# MINI_SAM_2017-01-010.net
KiCad netlist of a schematic drawn in EAGLE
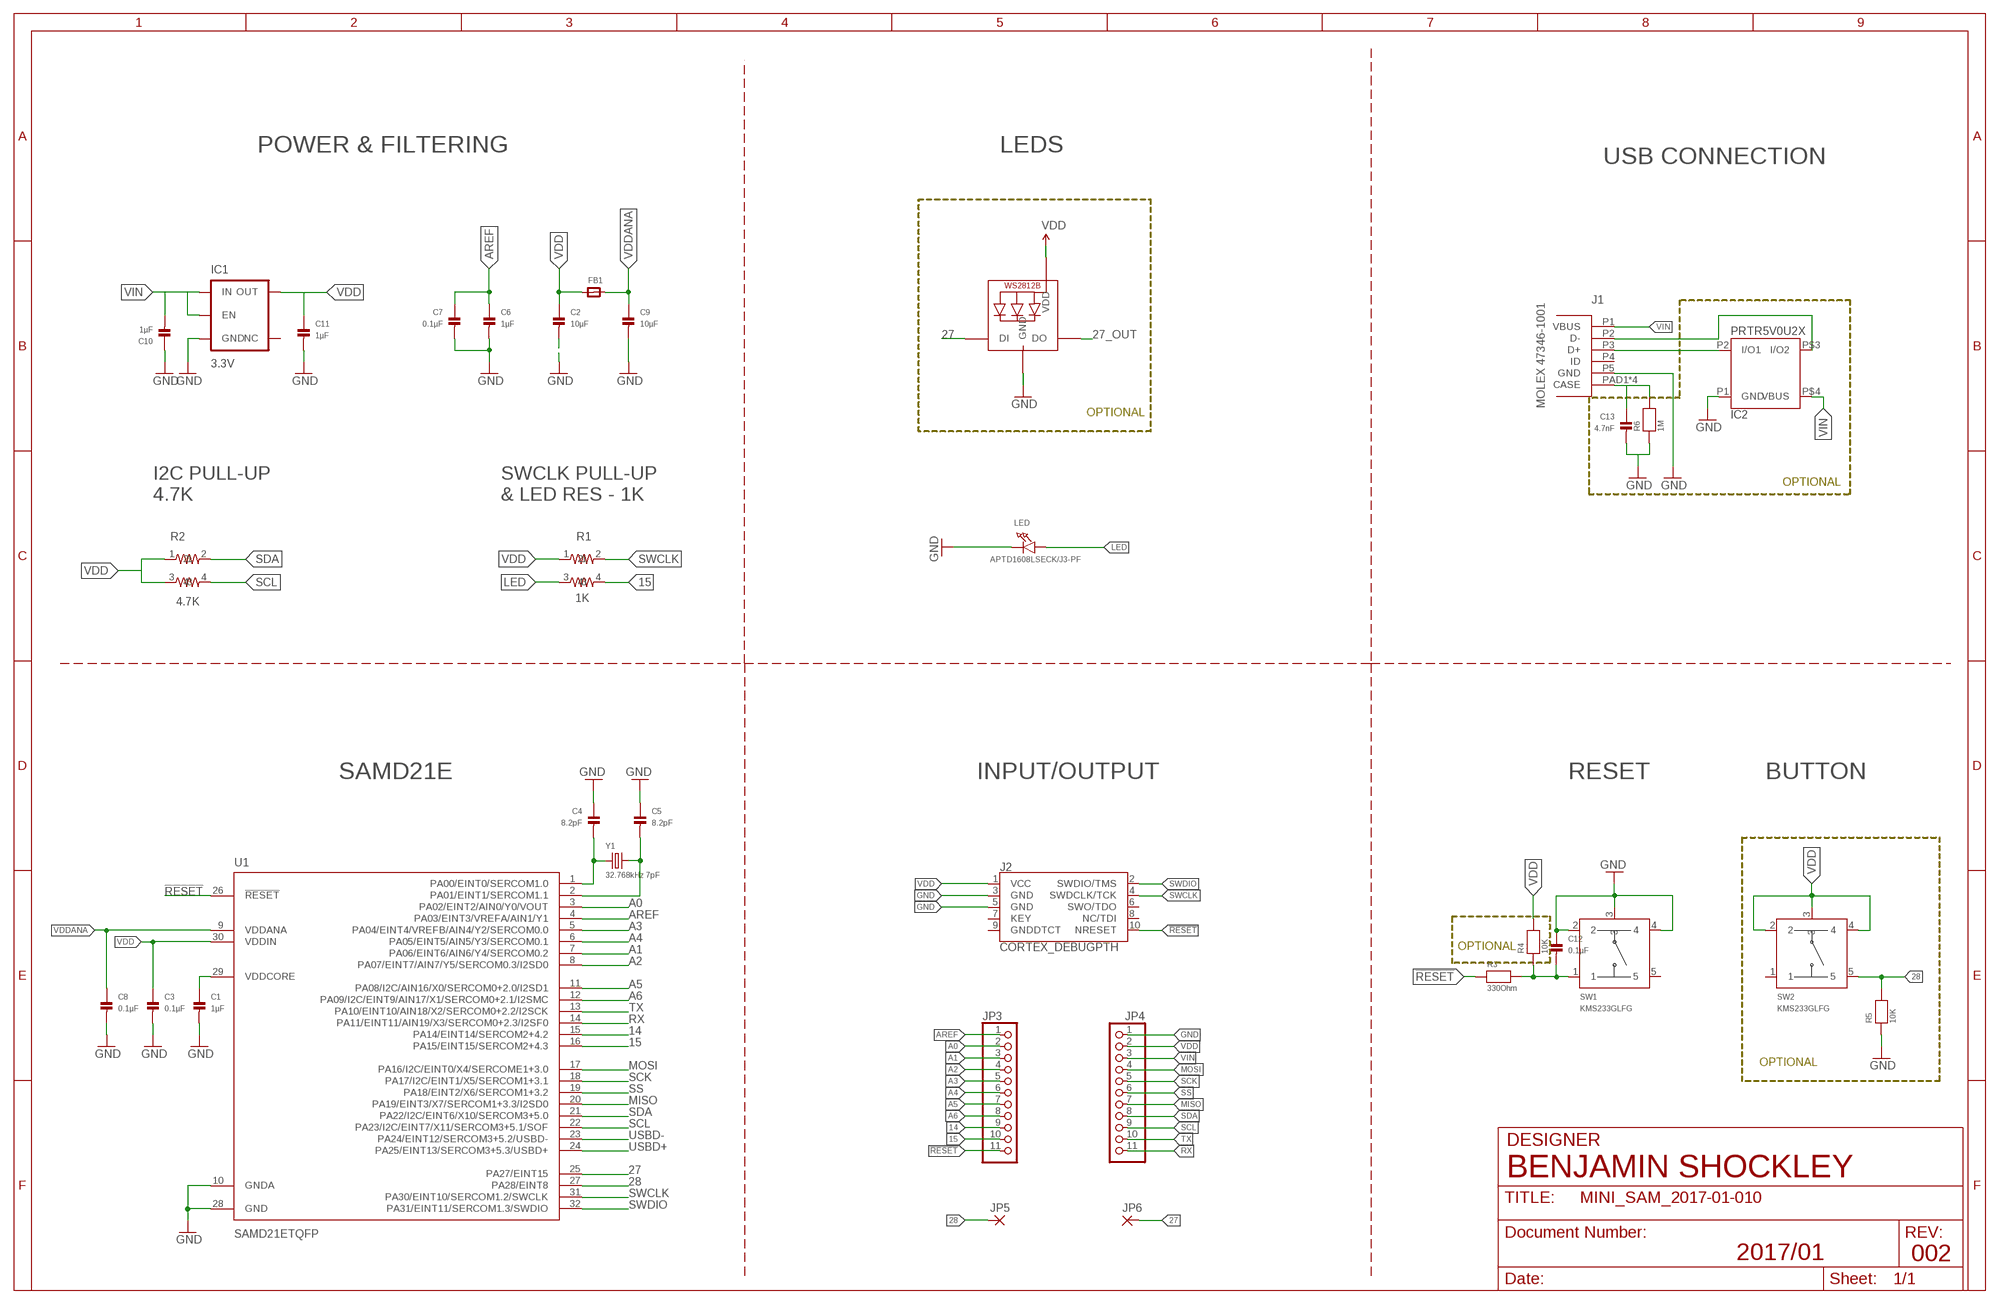
[diagram p0: schematic, sheet 1]

(export (version "E")
  (design (tool "Eeschema 10.0.6"))
  (components
    (comp (ref "C1")
      (value "1µF")
      (footprint "eagle-import:_0805MP")
      (libsource (lib "eagle-import") (part "CAP_CERAMIC_0805MP"))
    )
    (comp (ref "C2")
      (value "10µF")
      (footprint "eagle-import:_0805MP")
      (libsource (lib "eagle-import") (part "CAP_CERAMIC_0805MP"))
    )
    (comp (ref "C3")
      (value "0.1µF")
      (footprint "eagle-import:_0805MP")
      (libsource (lib "eagle-import") (part "CAP_CERAMIC_0805MP"))
    )
    (comp (ref "C4")
      (value "8.2pF")
      (footprint "eagle-import:_0805MP")
      (libsource (lib "eagle-import") (part "CAP_CERAMIC_0805MP"))
    )
    (comp (ref "C5")
      (value "8.2pF")
      (footprint "eagle-import:_0805MP")
      (libsource (lib "eagle-import") (part "CAP_CERAMIC_0805MP"))
    )
    (comp (ref "C6")
      (value "1µF")
      (footprint "eagle-import:_0805MP")
      (libsource (lib "eagle-import") (part "CAP_CERAMIC_0805MP"))
    )
    (comp (ref "C7")
      (value "0.1µF")
      (footprint "eagle-import:_0805MP")
      (libsource (lib "eagle-import") (part "CAP_CERAMIC_0805MP"))
    )
    (comp (ref "C8")
      (value "0.1µF")
      (footprint "eagle-import:_0805MP")
      (libsource (lib "eagle-import") (part "CAP_CERAMIC_0805MP"))
    )
    (comp (ref "C9")
      (value "10µF")
      (footprint "eagle-import:_0805MP")
      (libsource (lib "eagle-import") (part "CAP_CERAMIC_0805MP"))
    )
    (comp (ref "C10")
      (value "1µF")
      (footprint "eagle-import:_0805MP")
      (libsource (lib "eagle-import") (part "CAP_CERAMIC_0805MP"))
    )
    (comp (ref "C11")
      (value "1µF")
      (footprint "eagle-import:_0805MP")
      (libsource (lib "eagle-import") (part "CAP_CERAMIC_0805MP"))
    )
    (comp (ref "C12")
      (value "0.1µF")
      (footprint "eagle-import:_0805MP")
      (libsource (lib "eagle-import") (part "CAP_CERAMIC_0805MP"))
    )
    (comp (ref "C13")
      (value "4.7nF")
      (footprint "eagle-import:_0805MP")
      (libsource (lib "eagle-import") (part "CAP_CERAMIC_0805MP"))
    )
    (comp (ref "FB1")
      (value "FERRITE_0805MP")
      (footprint "eagle-import:_0805MP")
      (libsource (lib "eagle-import") (part "FERRITE_0805MP"))
    )
    (comp (ref "IC1")
      (value "3.3V")
      (footprint "eagle-import:SOT23-5")
      (libsource (lib "eagle-import") (part "V_REG_AP2112K-3.3V"))
    )
    (comp (ref "IC2")
      (value "PRTR5V0U2X")
      (footprint "eagle-import:SOT143B_REFLOW")
      (libsource (lib "eagle-import") (part "PRTR5V0U2X"))
    )
    (comp (ref "J1")
      (value "MOLEX_47346-100147346")
      (footprint "eagle-import:MOLEX_47346-1001")
      (libsource (lib "eagle-import") (part "MOLEX_47346-100147346"))
    )
    (comp (ref "J2")
      (value "CORTEX_DEBUGPTH")
      (footprint "eagle-import:2X5-PTH-1.27MM")
      (libsource (lib "eagle-import") (part "CORTEX_DEBUGPTH"))
    )
    (comp (ref "JP3")
      (value "PINHD-1X111X11_SMT")
      (footprint "eagle-import:1X11_SMT")
      (libsource (lib "eagle-import") (part "PINHD-1X111X11_SMT"))
    )
    (comp (ref "JP4")
      (value "PINHD-1X111X11_SMT")
      (footprint "eagle-import:1X11_SMT")
      (libsource (lib "eagle-import") (part "PINHD-1X111X11_SMT"))
    )
    (comp (ref "JP5")
      (value "FR11_PAD2MMX1MM")
      (footprint "eagle-import:SMD2MMX1MM")
      (libsource (lib "eagle-import") (part "FR11_PAD2MMX1MM"))
    )
    (comp (ref "JP6")
      (value "FR11_PAD2MMX1MM")
      (footprint "eagle-import:SMD2MMX1MM")
      (libsource (lib "eagle-import") (part "FR11_PAD2MMX1MM"))
    )
    (comp (ref "LED")
      (value "APTD1608LSECK/J3-PF")
      (footprint "eagle-import:CHIPLED_0603_NOOUTLINE")
      (libsource (lib "eagle-import") (part "LED0603_NOOUTLINE"))
    )
    (comp (ref "R1")
      (value "1K")
      (footprint "eagle-import:RESISTOR_ARRAY_0606")
      (libsource (lib "eagle-import") (part "RESISTOR_ARRAY_2"))
    )
    (comp (ref "R2")
      (value "4.7K")
      (footprint "eagle-import:RESISTOR_ARRAY_0606")
      (libsource (lib "eagle-import") (part "RESISTOR_ARRAY_2"))
    )
    (comp (ref "R3")
      (value "330Ohm")
      (footprint "eagle-import:_0805MP")
      (libsource (lib "eagle-import") (part "RESISTOR_0805MP"))
    )
    (comp (ref "R4")
      (value "10K")
      (footprint "eagle-import:_0805MP")
      (libsource (lib "eagle-import") (part "RESISTOR_0805MP"))
    )
    (comp (ref "R5")
      (value "10K")
      (footprint "eagle-import:_0805MP")
      (libsource (lib "eagle-import") (part "RESISTOR_0805MP"))
    )
    (comp (ref "R6")
      (value "1M")
      (footprint "eagle-import:_0805MP")
      (libsource (lib "eagle-import") (part "RESISTOR_0805MP"))
    )
    (comp (ref "STATUS")
      (value "WS2812B3535")
      (footprint "eagle-import:LED3535")
      (libsource (lib "eagle-import") (part "WS2812B3535"))
    )
    (comp (ref "SW1")
      (value "KMS233GLFG")
      (footprint "eagle-import:KMS_SWITCH")
      (libsource (lib "eagle-import") (part "KMS_SWITCHKMS"))
    )
    (comp (ref "SW2")
      (value "KMS233GLFG")
      (footprint "eagle-import:KMS_SWITCH")
      (libsource (lib "eagle-import") (part "KMS_SWITCHKMS"))
    )
    (comp (ref "U1")
      (value "SAMD21ETQFP")
      (footprint "eagle-import:TQFP32-08")
      (libsource (lib "eagle-import") (part "SAMD21ETQFP"))
    )
    (comp (ref "Y1")
      (value "32.768kHz 7pF")
      (footprint "eagle-import:_0805MP")
      (libsource (lib "eagle-import") (part "CRYSTAL0805PACKAGE"))
    )
  )
  (nets
    (net (code "1") (name "/27_OUT") (class "Default")
      (node (ref "STATUS") (pin "3") (pinfunction "DO_3") (pintype "output"))
    )
    (net (code "2") (name "/USBD+") (class "Default")
      (node (ref "IC2") (pin "P2") (pinfunction "I/O1_P2") (pintype "bidirectional"))
      (node (ref "J1") (pin "P3") (pinfunction "D+_P3") (pintype "bidirectional"))
      (node (ref "U1") (pin "24") (pinfunction "PA25/EINT13/SERCOM3+5.3/USBD+_24") (pintype "bidirectional"))
    )
    (net (code "3") (name "/USBD-") (class "Default")
      (node (ref "IC2") (pin "P$3") (pinfunction "I/O2_P$3") (pintype "bidirectional"))
      (node (ref "J1") (pin "P2") (pinfunction "D-_P2") (pintype "bidirectional"))
      (node (ref "U1") (pin "23") (pinfunction "PA24/EINT12/SERCOM3+5.2/USBD-_23") (pintype "bidirectional"))
    )
    (net (code "4") (name "/~{RESET}") (class "Default")
      (node (ref "J2") (pin "10") (pinfunction "NRESET_10") (pintype "bidirectional"))
      (node (ref "JP3") (pin "11") (pinfunction "11_11") (pintype "passive"))
      (node (ref "R3") (pin "1") (pinfunction "1_1") (pintype "passive"))
      (node (ref "U1") (pin "26") (pinfunction "~{RESET}_26") (pintype "bidirectional"))
    )
    (net (code "5") (name "14") (class "Default")
      (node (ref "JP3") (pin "9") (pinfunction "9_9") (pintype "passive"))
      (node (ref "U1") (pin "15") (pinfunction "PA14/EINT14/SERCOM2+4.2_15") (pintype "bidirectional"))
    )
    (net (code "6") (name "15") (class "Default")
      (node (ref "JP3") (pin "10") (pinfunction "10_10") (pintype "passive"))
      (node (ref "R1") (pin "4") (pinfunction "4_4") (pintype "passive"))
      (node (ref "U1") (pin "16") (pinfunction "PA15/EINT15/SERCOM2+4.3_16") (pintype "bidirectional"))
    )
    (net (code "7") (name "27") (class "Default")
      (node (ref "JP6") (pin "P$1") (pinfunction "P_P$1") (pintype "passive"))
      (node (ref "STATUS") (pin "1") (pinfunction "DI_1") (pintype "input"))
      (node (ref "U1") (pin "25") (pinfunction "PA27/EINT15_25") (pintype "bidirectional"))
    )
    (net (code "8") (name "28") (class "Default")
      (node (ref "JP5") (pin "P$1") (pinfunction "P_P$1") (pintype "passive"))
      (node (ref "R5") (pin "2") (pinfunction "2_2") (pintype "passive"))
      (node (ref "SW2") (pin "5") (pinfunction "5_5") (pintype "bidirectional"))
      (node (ref "U1") (pin "27") (pinfunction "PA28/EINT8_27") (pintype "bidirectional"))
    )
    (net (code "9") (name "A0") (class "Default")
      (node (ref "JP3") (pin "2") (pinfunction "2_2") (pintype "passive"))
      (node (ref "U1") (pin "3") (pinfunction "PA02/EINT2/AIN0/Y0/VOUT_3") (pintype "bidirectional"))
    )
    (net (code "10") (name "A1") (class "Default")
      (node (ref "JP3") (pin "3") (pinfunction "3_3") (pintype "passive"))
      (node (ref "U1") (pin "7") (pinfunction "PA06/EINT6/AIN6/Y4/SERCOM0.2_7") (pintype "bidirectional"))
    )
    (net (code "11") (name "A2") (class "Default")
      (node (ref "JP3") (pin "4") (pinfunction "4_4") (pintype "passive"))
      (node (ref "U1") (pin "8") (pinfunction "PA07/EINT7/AIN7/Y5/SERCOM0.3/I2SD0_8") (pintype "bidirectional"))
    )
    (net (code "12") (name "A3") (class "Default")
      (node (ref "JP3") (pin "5") (pinfunction "5_5") (pintype "passive"))
      (node (ref "U1") (pin "5") (pinfunction "PA04/EINT4/VREFB/AIN4/Y2/SERCOM0.0_5") (pintype "bidirectional"))
    )
    (net (code "13") (name "A4") (class "Default")
      (node (ref "JP3") (pin "6") (pinfunction "6_6") (pintype "passive"))
      (node (ref "U1") (pin "6") (pinfunction "PA05/EINT5/AIN5/Y3/SERCOM0.1_6") (pintype "bidirectional"))
    )
    (net (code "14") (name "A5") (class "Default")
      (node (ref "JP3") (pin "7") (pinfunction "7_7") (pintype "passive"))
      (node (ref "U1") (pin "11") (pinfunction "PA08/I2C/AIN16/X0/SERCOM0+2.0/I2SD1_11") (pintype "bidirectional"))
    )
    (net (code "15") (name "A6") (class "Default")
      (node (ref "JP3") (pin "8") (pinfunction "8_8") (pintype "passive"))
      (node (ref "U1") (pin "12") (pinfunction "PA09/I2C/EINT9/AIN17/X1/SERCOM0+2.1/I2SMC_12") (pintype "bidirectional"))
    )
    (net (code "16") (name "AREF") (class "Default")
      (node (ref "C6") (pin "1") (pinfunction "P$1_1") (pintype "passive"))
      (node (ref "C7") (pin "1") (pinfunction "P$1_1") (pintype "passive"))
      (node (ref "JP3") (pin "1") (pinfunction "1_1") (pintype "passive"))
      (node (ref "U1") (pin "4") (pinfunction "PA03/EINT3/VREFA/AIN1/Y1_4") (pintype "bidirectional"))
    )
    (net (code "17") (name "GND") (class "Default")
      (node (ref "C1") (pin "2") (pinfunction "P$2_2") (pintype "passive"))
      (node (ref "C10") (pin "1") (pinfunction "P$1_1") (pintype "passive"))
      (node (ref "C11") (pin "2") (pinfunction "P$2_2") (pintype "passive"))
      (node (ref "C12") (pin "1") (pinfunction "P$1_1") (pintype "passive"))
      (node (ref "C13") (pin "2") (pinfunction "P$2_2") (pintype "passive"))
      (node (ref "C2") (pin "2") (pinfunction "P$2_2") (pintype "passive"))
      (node (ref "C3") (pin "2") (pinfunction "P$2_2") (pintype "passive"))
      (node (ref "C4") (pin "1") (pinfunction "P$1_1") (pintype "passive"))
      (node (ref "C5") (pin "1") (pinfunction "P$1_1") (pintype "passive"))
      (node (ref "C6") (pin "2") (pinfunction "P$2_2") (pintype "passive"))
      (node (ref "C7") (pin "2") (pinfunction "P$2_2") (pintype "passive"))
      (node (ref "C8") (pin "2") (pinfunction "P$2_2") (pintype "passive"))
      (node (ref "C9") (pin "2") (pinfunction "P$2_2") (pintype "passive"))
      (node (ref "IC1") (pin "2") (pinfunction "GND_2") (pintype "input"))
      (node (ref "IC2") (pin "P1") (pinfunction "GND_P1") (pintype "bidirectional"))
      (node (ref "J1") (pin "P5") (pinfunction "GND_P5") (pintype "power_in"))
      (node (ref "J2") (pin "3") (pinfunction "GND_3") (pintype "bidirectional"))
      (node (ref "J2") (pin "5") (pinfunction "GND_5") (pintype "bidirectional"))
      (node (ref "JP4") (pin "1") (pinfunction "1_1") (pintype "passive"))
      (node (ref "LED") (pin "C") (pinfunction "C_C") (pintype "passive"))
      (node (ref "R5") (pin "1") (pinfunction "1_1") (pintype "passive"))
      (node (ref "R6") (pin "1") (pinfunction "1_1") (pintype "passive"))
      (node (ref "STATUS") (pin "4") (pinfunction "GND_4") (pintype "power_in"))
      (node (ref "SW1") (pin "2") (pinfunction "2_2") (pintype "bidirectional"))
      (node (ref "SW1") (pin "3") (pinfunction "3_3") (pintype "bidirectional"))
      (node (ref "SW1") (pin "4") (pinfunction "4_4") (pintype "bidirectional"))
      (node (ref "U1") (pin "10") (pinfunction "GNDA_10") (pintype "power_in"))
      (node (ref "U1") (pin "28") (pinfunction "GND_28") (pintype "power_in"))
    )
    (net (code "18") (name "LED") (class "Default")
      (node (ref "LED") (pin "A") (pinfunction "A_A") (pintype "passive"))
      (node (ref "R1") (pin "3") (pinfunction "3_3") (pintype "passive"))
    )
    (net (code "19") (name "MISO") (class "Default")
      (node (ref "JP4") (pin "7") (pinfunction "7_7") (pintype "passive"))
      (node (ref "U1") (pin "20") (pinfunction "PA19/EINT3/X7/SERCOM1+3.3/I2SD0_20") (pintype "bidirectional"))
    )
    (net (code "20") (name "MOSI") (class "Default")
      (node (ref "JP4") (pin "4") (pinfunction "4_4") (pintype "passive"))
      (node (ref "U1") (pin "17") (pinfunction "PA16/I2C/EINT0/X4/SERCOME1+3.0_17") (pintype "bidirectional"))
    )
    (net (code "21") (name "Net-(C1-P$1)") (class "Default")
      (node (ref "C1") (pin "1") (pinfunction "P$1_1") (pintype "passive"))
      (node (ref "U1") (pin "29") (pinfunction "VDDCORE_29") (pintype "power_in"))
    )
    (net (code "22") (name "Net-(C4-P$2)") (class "Default")
      (node (ref "C4") (pin "2") (pinfunction "P$2_2") (pintype "passive"))
      (node (ref "U1") (pin "1") (pinfunction "PA00/EINT0/SERCOM1.0_1") (pintype "bidirectional"))
      (node (ref "Y1") (pin "1") (pinfunction "1_1") (pintype "passive"))
    )
    (net (code "23") (name "Net-(C5-P$2)") (class "Default")
      (node (ref "C5") (pin "2") (pinfunction "P$2_2") (pintype "passive"))
      (node (ref "U1") (pin "2") (pinfunction "PA01/EINT1/SERCOM1.1_2") (pintype "bidirectional"))
      (node (ref "Y1") (pin "2") (pinfunction "2_2") (pintype "passive"))
    )
    (net (code "24") (name "Net-(C12-P$2)") (class "Default")
      (node (ref "C12") (pin "2") (pinfunction "P$2_2") (pintype "passive"))
      (node (ref "R3") (pin "2") (pinfunction "2_2") (pintype "passive"))
      (node (ref "R4") (pin "1") (pinfunction "1_1") (pintype "passive"))
      (node (ref "SW1") (pin "1") (pinfunction "1_1") (pintype "bidirectional"))
    )
    (net (code "25") (name "Net-(C13-P$1)") (class "Default")
      (node (ref "C13") (pin "1") (pinfunction "P$1_1") (pintype "passive"))
      (node (ref "J1") (pin "PAD1") (pinfunction "CASE_PAD1") (pintype "bidirectional"))
      (node (ref "J1") (pin "PAD2") (pinfunction "CASE_PAD2") (pintype "bidirectional"))
      (node (ref "J1") (pin "PAD3") (pinfunction "CASE_PAD3") (pintype "bidirectional"))
      (node (ref "J1") (pin "PAD4") (pinfunction "CASE_PAD4") (pintype "bidirectional"))
      (node (ref "R6") (pin "2") (pinfunction "2_2") (pintype "passive"))
    )
    (net (code "26") (name "RX") (class "Default")
      (node (ref "JP4") (pin "11") (pinfunction "11_11") (pintype "passive"))
      (node (ref "U1") (pin "14") (pinfunction "PA11/EINT11/AIN19/X3/SERCOM0+2.3/I2SF0_14") (pintype "bidirectional"))
    )
    (net (code "27") (name "SCK") (class "Default")
      (node (ref "JP4") (pin "5") (pinfunction "5_5") (pintype "passive"))
      (node (ref "U1") (pin "18") (pinfunction "PA17/I2C/EINT1/X5/SERCOM1+3.1_18") (pintype "bidirectional"))
    )
    (net (code "28") (name "SCL") (class "Default")
      (node (ref "JP4") (pin "9") (pinfunction "9_9") (pintype "passive"))
      (node (ref "R2") (pin "4") (pinfunction "4_4") (pintype "passive"))
      (node (ref "U1") (pin "22") (pinfunction "PA23/I2C/EINT7/X11/SERCOM3+5.1/SOF_22") (pintype "bidirectional"))
    )
    (net (code "29") (name "SDA") (class "Default")
      (node (ref "JP4") (pin "8") (pinfunction "8_8") (pintype "passive"))
      (node (ref "R2") (pin "2") (pinfunction "2_2") (pintype "passive"))
      (node (ref "U1") (pin "21") (pinfunction "PA22/I2C/EINT6/X10/SERCOM3+5.0_21") (pintype "bidirectional"))
    )
    (net (code "30") (name "SS") (class "Default")
      (node (ref "JP4") (pin "6") (pinfunction "6_6") (pintype "passive"))
      (node (ref "U1") (pin "19") (pinfunction "PA18/EINT2/X6/SERCOM1+3.2_19") (pintype "bidirectional"))
    )
    (net (code "31") (name "SWCLK") (class "Default")
      (node (ref "J2") (pin "4") (pinfunction "SWDCLK/TCK_4") (pintype "bidirectional"))
      (node (ref "R1") (pin "2") (pinfunction "2_2") (pintype "passive"))
      (node (ref "U1") (pin "31") (pinfunction "PA30/EINT10/SERCOM1.2/SWCLK_31") (pintype "bidirectional"))
    )
    (net (code "32") (name "SWDIO") (class "Default")
      (node (ref "J2") (pin "2") (pinfunction "SWDIO/TMS_2") (pintype "bidirectional"))
      (node (ref "U1") (pin "32") (pinfunction "PA31/EINT11/SERCOM1.3/SWDIO_32") (pintype "bidirectional"))
    )
    (net (code "33") (name "TX") (class "Default")
      (node (ref "JP4") (pin "10") (pinfunction "10_10") (pintype "passive"))
      (node (ref "U1") (pin "13") (pinfunction "PA10/EINT10/AIN18/X2/SERCOM0+2.2/I2SCK_13") (pintype "bidirectional"))
    )
    (net (code "34") (name "VDD") (class "Default")
      (node (ref "C11") (pin "1") (pinfunction "P$1_1") (pintype "passive"))
      (node (ref "C2") (pin "1") (pinfunction "P$1_1") (pintype "passive"))
      (node (ref "C3") (pin "1") (pinfunction "P$1_1") (pintype "passive"))
      (node (ref "FB1") (pin "1") (pinfunction "P$1_1") (pintype "passive"))
      (node (ref "IC1") (pin "5") (pinfunction "OUT_5") (pintype "passive"))
      (node (ref "J2") (pin "1") (pinfunction "VCC_1") (pintype "bidirectional"))
      (node (ref "JP4") (pin "2") (pinfunction "2_2") (pintype "passive"))
      (node (ref "R1") (pin "1") (pinfunction "1_1") (pintype "passive"))
      (node (ref "R2") (pin "1") (pinfunction "1_1") (pintype "passive"))
      (node (ref "R2") (pin "3") (pinfunction "3_3") (pintype "passive"))
      (node (ref "R4") (pin "2") (pinfunction "2_2") (pintype "passive"))
      (node (ref "STATUS") (pin "2") (pinfunction "VDD_2") (pintype "power_in"))
      (node (ref "SW2") (pin "2") (pinfunction "2_2") (pintype "bidirectional"))
      (node (ref "SW2") (pin "3") (pinfunction "3_3") (pintype "bidirectional"))
      (node (ref "SW2") (pin "4") (pinfunction "4_4") (pintype "bidirectional"))
      (node (ref "U1") (pin "30") (pinfunction "VDDIN_30") (pintype "power_in"))
    )
    (net (code "35") (name "VDDANA") (class "Default")
      (node (ref "C8") (pin "1") (pinfunction "P$1_1") (pintype "passive"))
      (node (ref "C9") (pin "1") (pinfunction "P$1_1") (pintype "passive"))
      (node (ref "FB1") (pin "2") (pinfunction "P$2_2") (pintype "passive"))
      (node (ref "U1") (pin "9") (pinfunction "VDDANA_9") (pintype "power_in"))
    )
    (net (code "36") (name "VIN") (class "Default")
      (node (ref "C10") (pin "2") (pinfunction "P$2_2") (pintype "passive"))
      (node (ref "IC1") (pin "1") (pinfunction "IN_1") (pintype "input"))
      (node (ref "IC1") (pin "3") (pinfunction "EN_3") (pintype "input"))
      (node (ref "IC2") (pin "P$4") (pinfunction "VBUS_P$4") (pintype "bidirectional"))
      (node (ref "J1") (pin "P1") (pinfunction "VBUS_P1") (pintype "power_in"))
      (node (ref "JP4") (pin "3") (pinfunction "3_3") (pintype "passive"))
    )
    (net (code "37") (name "unconnected-(IC1-NC-Pad4)") (class "Default")
      (node (ref "IC1") (pin "4") (pinfunction "NC_4") (pintype "input"))
    )
    (net (code "38") (name "unconnected-(J1-ID-PadP4)") (class "Default")
      (node (ref "J1") (pin "P4") (pinfunction "ID_P4") (pintype "bidirectional"))
    )
    (net (code "39") (name "unconnected-(J2-GNDDTCT-Pad9)") (class "Default")
      (node (ref "J2") (pin "9") (pinfunction "GNDDTCT_9") (pintype "bidirectional"))
    )
    (net (code "40") (name "unconnected-(J2-KEY-Pad7)") (class "Default")
      (node (ref "J2") (pin "7") (pinfunction "KEY_7") (pintype "bidirectional"))
    )
    (net (code "41") (name "unconnected-(J2-NC{slash}TDI-Pad8)") (class "Default")
      (node (ref "J2") (pin "8") (pinfunction "NC/TDI_8") (pintype "bidirectional"))
    )
    (net (code "42") (name "unconnected-(J2-SWO{slash}TDO-Pad6)") (class "Default")
      (node (ref "J2") (pin "6") (pinfunction "SWO/TDO_6") (pintype "bidirectional"))
    )
    (net (code "43") (name "unconnected-(SW1-Pad5)") (class "Default")
      (node (ref "SW1") (pin "5") (pinfunction "5_5") (pintype "bidirectional"))
    )
    (net (code "44") (name "unconnected-(SW2-Pad1)") (class "Default")
      (node (ref "SW2") (pin "1") (pinfunction "1_1") (pintype "bidirectional"))
    )
  )
)
